# ToF.net
KiCad netlist of a schematic drawn in Altium Designer
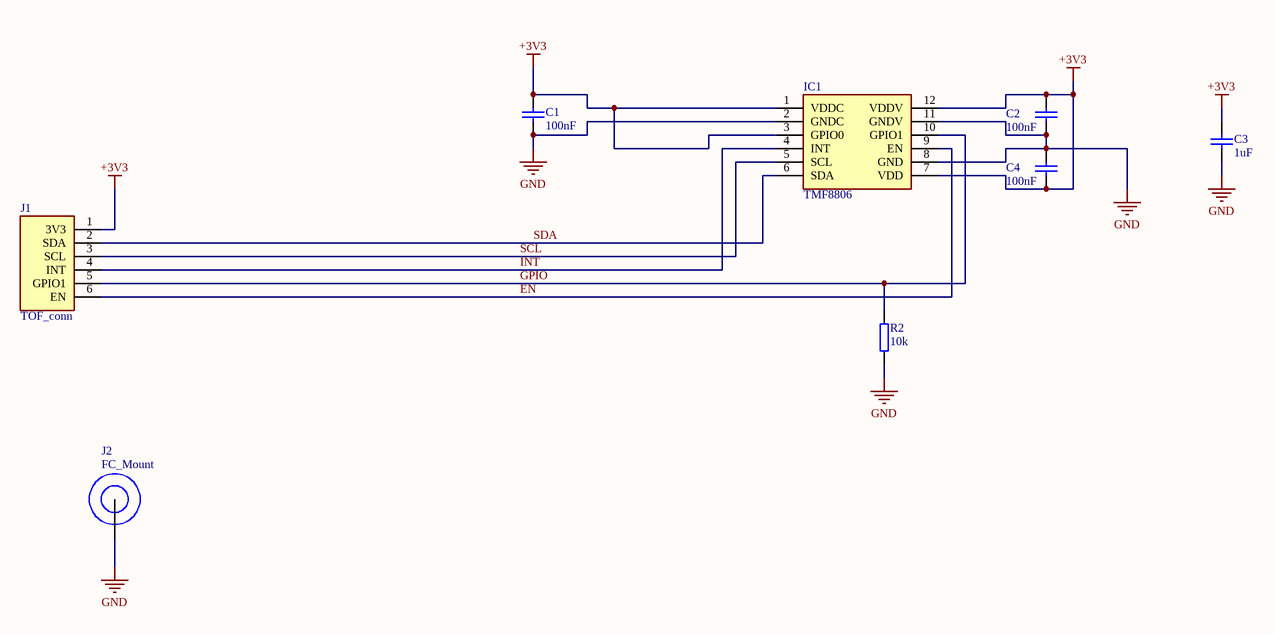
[diagram p0: ToF.SchDoc]

(export (version "E")
  (design (tool "Eeschema 10.0.6"))
  (components
    (comp (ref "C1")
      (value "100nF")
      (footprint "CAP0402")
      (fields
        (field (name "VOLTAGE") "6V3")
        (field (name "MANUFACTURER_PART_NUMBER") "GRM155R71H104ME14D")
        (field (name "Comment") "Cap0402")
      )
      (libsource (lib "capacitorsSMD") (part "Cap0402"))
    )
    (comp (ref "C2")
      (value "100nF")
      (footprint "CAP0402")
      (fields
        (field (name "VOLTAGE") "6V3")
        (field (name "MANUFACTURER_PART_NUMBER") "GRM155R71H104ME14D")
        (field (name "Comment") "Cap0402")
      )
      (libsource (lib "capacitorsSMD") (part "Cap0402"))
    )
    (comp (ref "C3")
      (value "1uF")
      (footprint "CAP0603")
      (fields
        (field (name "VOLTAGE") "25V")
        (field (name "MANUFACTURER_PART_NUMBER") "GRT188R61H105KE13D")
        (field (name "Comment") "Cap0603")
      )
      (libsource (lib "capacitorsSMD") (part "Cap0603"))
    )
    (comp (ref "C4")
      (value "100nF")
      (footprint "CAP0402")
      (fields
        (field (name "VOLTAGE") "6V3")
        (field (name "MANUFACTURER_PART_NUMBER") "GRM155R71H104ME14D")
        (field (name "Comment") "Cap0402")
      )
      (libsource (lib "capacitorsSMD") (part "Cap0402"))
    )
    (comp (ref "IC1")
      (value "TMF8806")
      (footprint "SamacSys:TMF88051B")
      (description "Integrated Circuit")
      (fields
        (field (name "MANUFACTURER_PART_NUMBER") "TMF8805-1B")
        (field (name "MOUSER PART NUMBER") "985-TMF8805-1B")
      )
      (libsource (lib "*") (part "TMF8805-1B"))
    )
    (comp (ref "J1")
      (value "TOF_conn")
      (footprint "SamacSys:PCBComponent_1")
      (libsource (lib "SamacSys") (part "TOF_conn"))
    )
    (comp (ref "J2")
      (value "FC_Mount")
      (footprint "SamacSys:FC_Mount")
      (libsource (lib "SamacSys") (part "FC_Mount"))
    )
    (comp (ref "R2")
      (value "10k")
      (footprint "RES0402")
      (fields (field (name "MANUFACTURER_PART_NUMBER") "ERA-2AED103X") (field (name "Comment") "Res0402"))
      (libsource (lib "resistorSMD") (part "Res0402"))
    )
  )
  (nets
    (net (code "1") (name "+3V3") (class "Default")
      (node (ref "C1") (pin "2") (pinfunction "2_2") (pintype "passive"))
      (node (ref "C2") (pin "2") (pinfunction "2_2") (pintype "passive"))
      (node (ref "C3") (pin "2") (pinfunction "2_2") (pintype "passive"))
      (node (ref "C4") (pin "1") (pinfunction "1_1") (pintype "passive"))
      (node (ref "IC1") (pin "1") (pinfunction "VDDC_1") (pintype "passive"))
      (node (ref "IC1") (pin "12") (pinfunction "VDDV_12") (pintype "passive"))
      (node (ref "IC1") (pin "3") (pinfunction "GPIO0_3") (pintype "passive"))
      (node (ref "IC1") (pin "7") (pinfunction "VDD_7") (pintype "passive"))
      (node (ref "J1") (pin "1") (pinfunction "3V3_1") (pintype "passive"))
    )
    (net (code "2") (name "/EN") (class "Default")
      (node (ref "IC1") (pin "9") (pinfunction "EN_9") (pintype "passive"))
      (node (ref "J1") (pin "6") (pinfunction "EN_6") (pintype "passive"))
    )
    (net (code "3") (name "/GPIO") (class "Default")
      (node (ref "IC1") (pin "10") (pinfunction "GPIO1_10") (pintype "passive"))
      (node (ref "J1") (pin "5") (pinfunction "GPIO1_5") (pintype "passive"))
      (node (ref "R2") (pin "2") (pinfunction "2_2") (pintype "passive"))
    )
    (net (code "4") (name "/INT") (class "Default")
      (node (ref "IC1") (pin "4") (pinfunction "INT_4") (pintype "passive"))
      (node (ref "J1") (pin "4") (pinfunction "INT_4") (pintype "passive"))
    )
    (net (code "5") (name "/SCL") (class "Default")
      (node (ref "IC1") (pin "5") (pinfunction "SCL_5") (pintype "passive"))
      (node (ref "J1") (pin "3") (pinfunction "SCL_3") (pintype "passive"))
    )
    (net (code "6") (name "/SDA") (class "Default")
      (node (ref "IC1") (pin "6") (pinfunction "SDA_6") (pintype "passive"))
      (node (ref "J1") (pin "2") (pinfunction "SDA_2") (pintype "passive"))
    )
    (net (code "7") (name "GND") (class "Default")
      (node (ref "C1") (pin "1") (pinfunction "1_1") (pintype "passive"))
      (node (ref "C2") (pin "1") (pinfunction "1_1") (pintype "passive"))
      (node (ref "C3") (pin "1") (pinfunction "1_1") (pintype "passive"))
      (node (ref "C4") (pin "2") (pinfunction "2_2") (pintype "passive"))
      (node (ref "IC1") (pin "11") (pinfunction "GNDV_11") (pintype "passive"))
      (node (ref "IC1") (pin "2") (pinfunction "GNDC_2") (pintype "passive"))
      (node (ref "IC1") (pin "8") (pinfunction "GND_8") (pintype "passive"))
      (node (ref "J2") (pin "1") (pinfunction "1_1") (pintype "passive"))
      (node (ref "R2") (pin "1") (pinfunction "1_1") (pintype "passive"))
    )
  )
)
